# Sheet1.net
KiCad netlist of a schematic drawn in Altium Designer
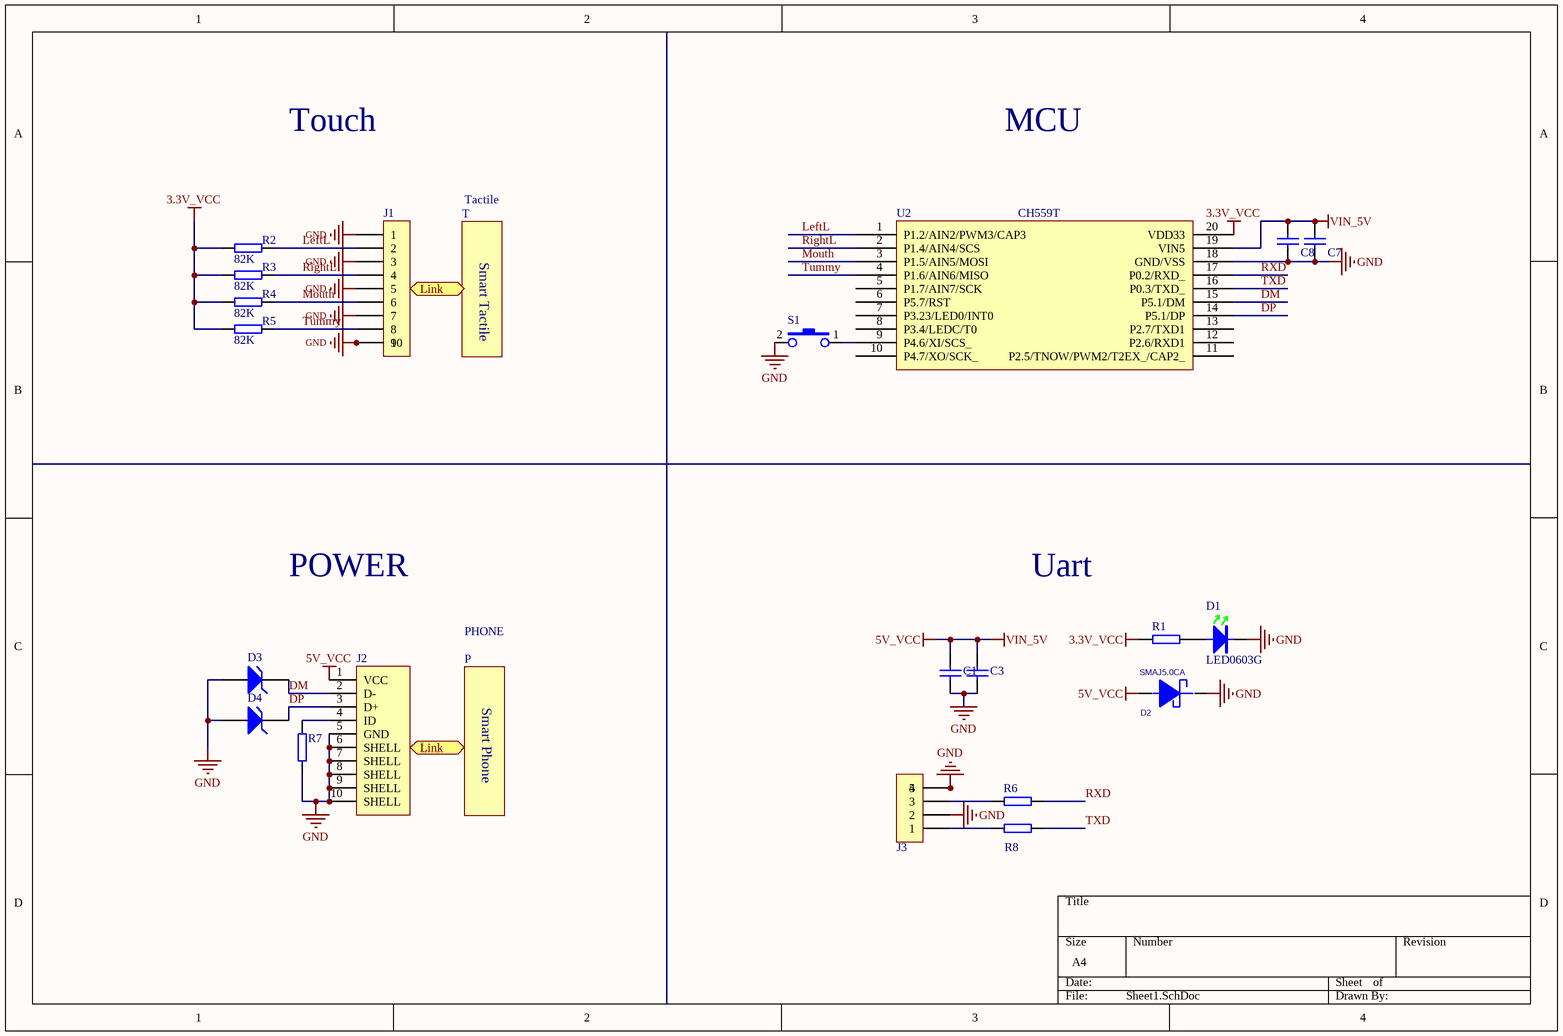
[diagram p0: Sheet1.SchDoc]

(export (version "E")
  (design (tool "Eeschema 10.0.6"))
  (components
    (comp (ref "C1")
      (value "226M50V")
      (footprint "C0805")
      (description "贴片电容-陶瓷")
      (libsource (lib "AIWAC-bolsterV01") (part "C0805Y5V-226M50V"))
    )
    (comp (ref "C3")
      (value "105K16V")
      (footprint "C0603")
      (description "贴片电容-陶瓷")
      (libsource (lib "AIWAC-bolsterV01") (part "C0603X7R-105K16V"))
    )
    (comp (ref "C7")
      (value "106K50V")
      (footprint "C0603")
      (description "贴片电容-陶瓷")
      (libsource (lib "AIWAC-bolsterV01") (part "C0603X7R-106K50V"))
    )
    (comp (ref "C8")
      (value "104K50V")
      (footprint "C0603")
      (description "贴片电容-陶瓷")
      (libsource (lib "epic2") (part "C0603X7R-104K50V"))
    )
    (comp (ref "D1")
      (value "LED0603G")
      (footprint "D-LED0603G")
      (description "贴片二极管-LED")
      (libsource (lib "AIWAC-bolsterV01") (part "DLED-0603-G"))
    )
    (comp (ref "D2") (value "SMAJ5.0CA") (footprint "DO-214") (libsource (lib "epic2") (part "SMAJ5.0CA")))
    (comp (ref "D3")
      (value "ESDA_TR1/0603")
      (footprint "HS_0603D")
      (description "Zener Diode")
      (fields (field (name "PUBLISHER") "*"))
      (libsource (lib "HSC32K1(QFN56)_BlueTooth_V2.0_20171108 - 副本") (part "D Zener"))
    )
    (comp (ref "D4")
      (value "ESDA_TR1/0603")
      (footprint "HS_0603D")
      (description "Zener Diode")
      (fields (field (name "PUBLISHER") "*"))
      (libsource (lib "HSC32K1(QFN56)_BlueTooth_V2.0_20171108 - 副本") (part "D Zener"))
    )
    (comp (ref "J1")
      (value "SH1.0-T-1-LT-8A_卧式")
      (footprint "J-SH1.0-T-1-LT-8A_卧式")
      (description "SH1.0-T-1-LT-6A_卧式")
      (libsource (lib "Connector") (part "SH1.0-T-1-LT-8A_卧式"))
    )
    (comp (ref "J2")
      (value "USB-MINI-SOCKET")
      (footprint "MICRO-USB - 5.9")
      (description "USB-A卧式插座")
      (libsource (lib "EPIC") (part "J-USB-MINI-SOCKET"))
    )
    (comp (ref "J3")
      (value "SH1.0-T-1-LT-3A_卧式")
      (footprint "J-SH1.0-T-1-LT-3A_卧式")
      (libsource (lib "Connector") (part "SH1.0-T-1-LT-3A_卧式"))
    )
    (comp (ref "P") (value "PHONE") (libsource (lib "EPIC") (part "PHONE")))
    (comp (ref "R1")
      (value "2K")
      (footprint "R0603")
      (description "贴片电阻-通用")
      (libsource (lib "Resistor") (part "R0603-100RF"))
    )
    (comp (ref "R2")
      (value "82K")
      (footprint "R0603")
      (description "贴片电阻-通用")
      (libsource (lib "Resistor") (part "R0603-100RF"))
    )
    (comp (ref "R3")
      (value "82K")
      (footprint "R0603")
      (description "贴片电阻-通用")
      (libsource (lib "Resistor") (part "R0603-100RF"))
    )
    (comp (ref "R4")
      (value "82K")
      (footprint "R0603")
      (description "贴片电阻-通用")
      (libsource (lib "Resistor") (part "R0603-100RF"))
    )
    (comp (ref "R5")
      (value "82K")
      (footprint "R0603")
      (description "贴片电阻-通用")
      (libsource (lib "Resistor") (part "R0603-100RF"))
    )
    (comp (ref "R6")
      (value "22R")
      (footprint "R0603")
      (description "贴片电阻-通用")
      (libsource (lib "Resistor") (part "R0603-100RF"))
    )
    (comp (ref "R7")
      (value "0R")
      (footprint "R0603")
      (description "贴片电阻-通用")
      (libsource (lib "EPIC") (part "R0603-0R"))
    )
    (comp (ref "R8")
      (value "22R")
      (footprint "R0603")
      (description "贴片电阻-通用")
      (libsource (lib "Resistor") (part "R0603-100RF"))
    )
    (comp (ref "S1")
      (value "2*3*0.65")
      (footprint "S-K2*3 - duplicate")
      (description "薄膜按键")
      (libsource (lib "Key") (part "2*3*0.65 薄膜按键"))
    )
    (comp (ref "T") (value "Tactile") (libsource (lib "EPIC") (part "Tactile")))
    (comp (ref "U2")
      (value "CH559T")
      (footprint "TSSOP20")
      (description "usb通信")
      (libsource (lib "EPIC") (part "CH559T"))
    )
  )
  (nets
    (net (code "1") (name "/DM") (class "Default")
      (node (ref "D3") (pin "2") (pinfunction "K_2") (pintype "passive"))
      (node (ref "J2") (pin "2") (pinfunction "D-_2") (pintype "passive"))
      (node (ref "U2") (pin "15") (pinfunction "P5.1/DM_15") (pintype "passive"))
    )
    (net (code "2") (name "/DP") (class "Default")
      (node (ref "D4") (pin "2") (pinfunction "K_2") (pintype "passive"))
      (node (ref "J2") (pin "3") (pinfunction "D+_3") (pintype "passive"))
      (node (ref "U2") (pin "14") (pinfunction "P5.1/DP_14") (pintype "passive"))
    )
    (net (code "3") (name "/LeftL") (class "Default")
      (node (ref "J1") (pin "2") (pinfunction "2_2") (pintype "passive"))
      (node (ref "R2") (pin "2") (pinfunction "2_2") (pintype "passive"))
      (node (ref "U2") (pin "1") (pinfunction "P1.2/AIN2/PWM3/CAP3_1") (pintype "passive"))
    )
    (net (code "5") (name "/Mouth") (class "Default")
      (node (ref "J1") (pin "6") (pinfunction "6_6") (pintype "passive"))
      (node (ref "R4") (pin "2") (pinfunction "2_2") (pintype "passive"))
      (node (ref "U2") (pin "3") (pinfunction "P1.5/AIN5/MOSI_3") (pintype "passive"))
    )
    (net (code "6") (name "/RXD") (class "Default")
      (node (ref "R6") (pin "1") (pinfunction "1_1") (pintype "passive"))
      (node (ref "U2") (pin "17") (pinfunction "P0.2/RXD__17") (pintype "passive"))
    )
    (net (code "7") (name "/RightL") (class "Default")
      (node (ref "J1") (pin "4") (pinfunction "4_4") (pintype "passive"))
      (node (ref "R3") (pin "2") (pinfunction "2_2") (pintype "passive"))
      (node (ref "U2") (pin "2") (pinfunction "P1.4/AIN4/SCS_2") (pintype "passive"))
    )
    (net (code "8") (name "/TXD") (class "Default")
      (node (ref "R8") (pin "1") (pinfunction "1_1") (pintype "passive"))
      (node (ref "U2") (pin "16") (pinfunction "P0.3/TXD__16") (pintype "passive"))
    )
    (net (code "9") (name "/Tummy") (class "Default")
      (node (ref "J1") (pin "8") (pinfunction "8_8") (pintype "passive"))
      (node (ref "R5") (pin "2") (pinfunction "2_2") (pintype "passive"))
      (node (ref "U2") (pin "4") (pinfunction "P1.6/AIN6/MISO_4") (pintype "passive"))
    )
    (net (code "10") (name "3.3V_VCC") (class "Default")
      (node (ref "R1") (pin "2") (pinfunction "2_2") (pintype "passive"))
      (node (ref "R2") (pin "1") (pinfunction "1_1") (pintype "passive"))
      (node (ref "R3") (pin "1") (pinfunction "1_1") (pintype "passive"))
      (node (ref "R4") (pin "1") (pinfunction "1_1") (pintype "passive"))
      (node (ref "R5") (pin "1") (pinfunction "1_1") (pintype "passive"))
      (node (ref "U2") (pin "20") (pinfunction "VDD33_20") (pintype "passive"))
    )
    (net (code "11") (name "5V_VCC") (class "Default")
      (node (ref "C1") (pin "1") (pinfunction "1_1") (pintype "passive"))
      (node (ref "C3") (pin "1") (pinfunction "1_1") (pintype "passive"))
      (node (ref "C7") (pin "2") (pinfunction "2_2") (pintype "passive"))
      (node (ref "C8") (pin "1") (pinfunction "1_1") (pintype "passive"))
      (node (ref "D2") (pin "1") (pinfunction "+_1") (pintype "passive"))
      (node (ref "J2") (pin "1") (pinfunction "VCC_1") (pintype "passive"))
      (node (ref "U2") (pin "19") (pinfunction "VIN5_19") (pintype "passive"))
    )
    (net (code "12") (name "GND") (class "Default")
      (node (ref "C1") (pin "2") (pinfunction "2_2") (pintype "passive"))
      (node (ref "C3") (pin "2") (pinfunction "2_2") (pintype "passive"))
      (node (ref "C7") (pin "1") (pinfunction "1_1") (pintype "passive"))
      (node (ref "C8") (pin "2") (pinfunction "2_2") (pintype "passive"))
      (node (ref "D1") (pin "2") (pinfunction "2_2") (pintype "passive"))
      (node (ref "D2") (pin "2") (pinfunction "-_2") (pintype "passive"))
      (node (ref "D3") (pin "1") (pinfunction "A_1") (pintype "passive"))
      (node (ref "D4") (pin "1") (pinfunction "A_1") (pintype "passive"))
      (node (ref "J1") (pin "1") (pinfunction "1_1") (pintype "passive"))
      (node (ref "J1") (pin "10") (pinfunction "10_10") (pintype "passive"))
      (node (ref "J1") (pin "3") (pinfunction "3_3") (pintype "passive"))
      (node (ref "J1") (pin "5") (pinfunction "5_5") (pintype "passive"))
      (node (ref "J1") (pin "7") (pinfunction "7_7") (pintype "passive"))
      (node (ref "J1") (pin "9") (pinfunction "9_9") (pintype "passive"))
      (node (ref "J2") (pin "10") (pinfunction "SHELL_10") (pintype "passive"))
      (node (ref "J2") (pin "5") (pinfunction "GND_5") (pintype "passive"))
      (node (ref "J2") (pin "6") (pinfunction "SHELL_6") (pintype "passive"))
      (node (ref "J2") (pin "7") (pinfunction "SHELL_7") (pintype "passive"))
      (node (ref "J2") (pin "8") (pinfunction "SHELL_8") (pintype "passive"))
      (node (ref "J2") (pin "9") (pinfunction "SHELL_9") (pintype "passive"))
      (node (ref "J3") (pin "2") (pinfunction "2_2") (pintype "passive"))
      (node (ref "J3") (pin "4") (pinfunction "4_4") (pintype "passive"))
      (node (ref "J3") (pin "5") (pinfunction "5_5") (pintype "passive"))
      (node (ref "R7") (pin "1") (pinfunction "1_1") (pintype "passive"))
      (node (ref "S1") (pin "2") (pinfunction "2_2") (pintype "passive"))
      (node (ref "U2") (pin "18") (pinfunction "GND/VSS_18") (pintype "passive"))
    )
    (net (code "13") (name "Net-(D1-Pad1)") (class "Default")
      (node (ref "D1") (pin "1") (pinfunction "1_1") (pintype "passive"))
      (node (ref "R1") (pin "1") (pinfunction "1_1") (pintype "passive"))
    )
    (net (code "14") (name "Net-(J2-ID)") (class "Default")
      (node (ref "J2") (pin "4") (pinfunction "ID_4") (pintype "passive"))
      (node (ref "R7") (pin "2") (pinfunction "2_2") (pintype "passive"))
    )
    (net (code "15") (name "Net-(J3-Pad1)") (class "Default")
      (node (ref "J3") (pin "1") (pinfunction "1_1") (pintype "passive"))
      (node (ref "R8") (pin "2") (pinfunction "2_2") (pintype "passive"))
    )
    (net (code "16") (name "Net-(J3-Pad3)") (class "Default")
      (node (ref "J3") (pin "3") (pinfunction "3_3") (pintype "passive"))
      (node (ref "R6") (pin "2") (pinfunction "2_2") (pintype "passive"))
    )
    (net (code "17") (name "Net-(U2-P4.6{slash}XI{slash}SCS_)") (class "Default")
      (node (ref "S1") (pin "1") (pinfunction "1_1") (pintype "passive"))
      (node (ref "U2") (pin "9") (pinfunction "P4.6/XI/SCS__9") (pintype "passive"))
    )
    (net (code "18") (name "unconnected-(U2-P1.7{slash}AIN7{slash}SCK-Pad5)") (class "Default")
      (node (ref "U2") (pin "5") (pinfunction "P1.7/AIN7/SCK_5") (pintype "passive"))
    )
    (net (code "19") (name "unconnected-(U2-P2.5{slash}TNOW{slash}PWM2{slash}T2EX_{slash}CAP2_-Pad11)") (class "Default")
      (node (ref "U2") (pin "11") (pinfunction "P2.5/TNOW/PWM2/T2EX_/CAP2__11") (pintype "passive"))
    )
    (net (code "20") (name "unconnected-(U2-P2.6{slash}RXD1-Pad12)") (class "Default")
      (node (ref "U2") (pin "12") (pinfunction "P2.6/RXD1_12") (pintype "passive"))
    )
    (net (code "21") (name "unconnected-(U2-P2.7{slash}TXD1-Pad13)") (class "Default")
      (node (ref "U2") (pin "13") (pinfunction "P2.7/TXD1_13") (pintype "passive"))
    )
    (net (code "22") (name "unconnected-(U2-P3.4{slash}LEDC{slash}T0-Pad8)") (class "Default")
      (node (ref "U2") (pin "8") (pinfunction "P3.4/LEDC/T0_8") (pintype "passive"))
    )
    (net (code "23") (name "unconnected-(U2-P3.23{slash}LED0{slash}INT0-Pad7)") (class "Default")
      (node (ref "U2") (pin "7") (pinfunction "P3.23/LED0/INT0_7") (pintype "passive"))
    )
    (net (code "24") (name "unconnected-(U2-P4.7{slash}XO{slash}SCK_-Pad10)") (class "Default")
      (node (ref "U2") (pin "10") (pinfunction "P4.7/XO/SCK__10") (pintype "passive"))
    )
    (net (code "25") (name "unconnected-(U2-P5.7{slash}RST-Pad6)") (class "Default")
      (node (ref "U2") (pin "6") (pinfunction "P5.7/RST_6") (pintype "passive"))
    )
  )
)
